# 06_B_RLight.net
KiCad netlist of a schematic drawn in EasyEDA Pro
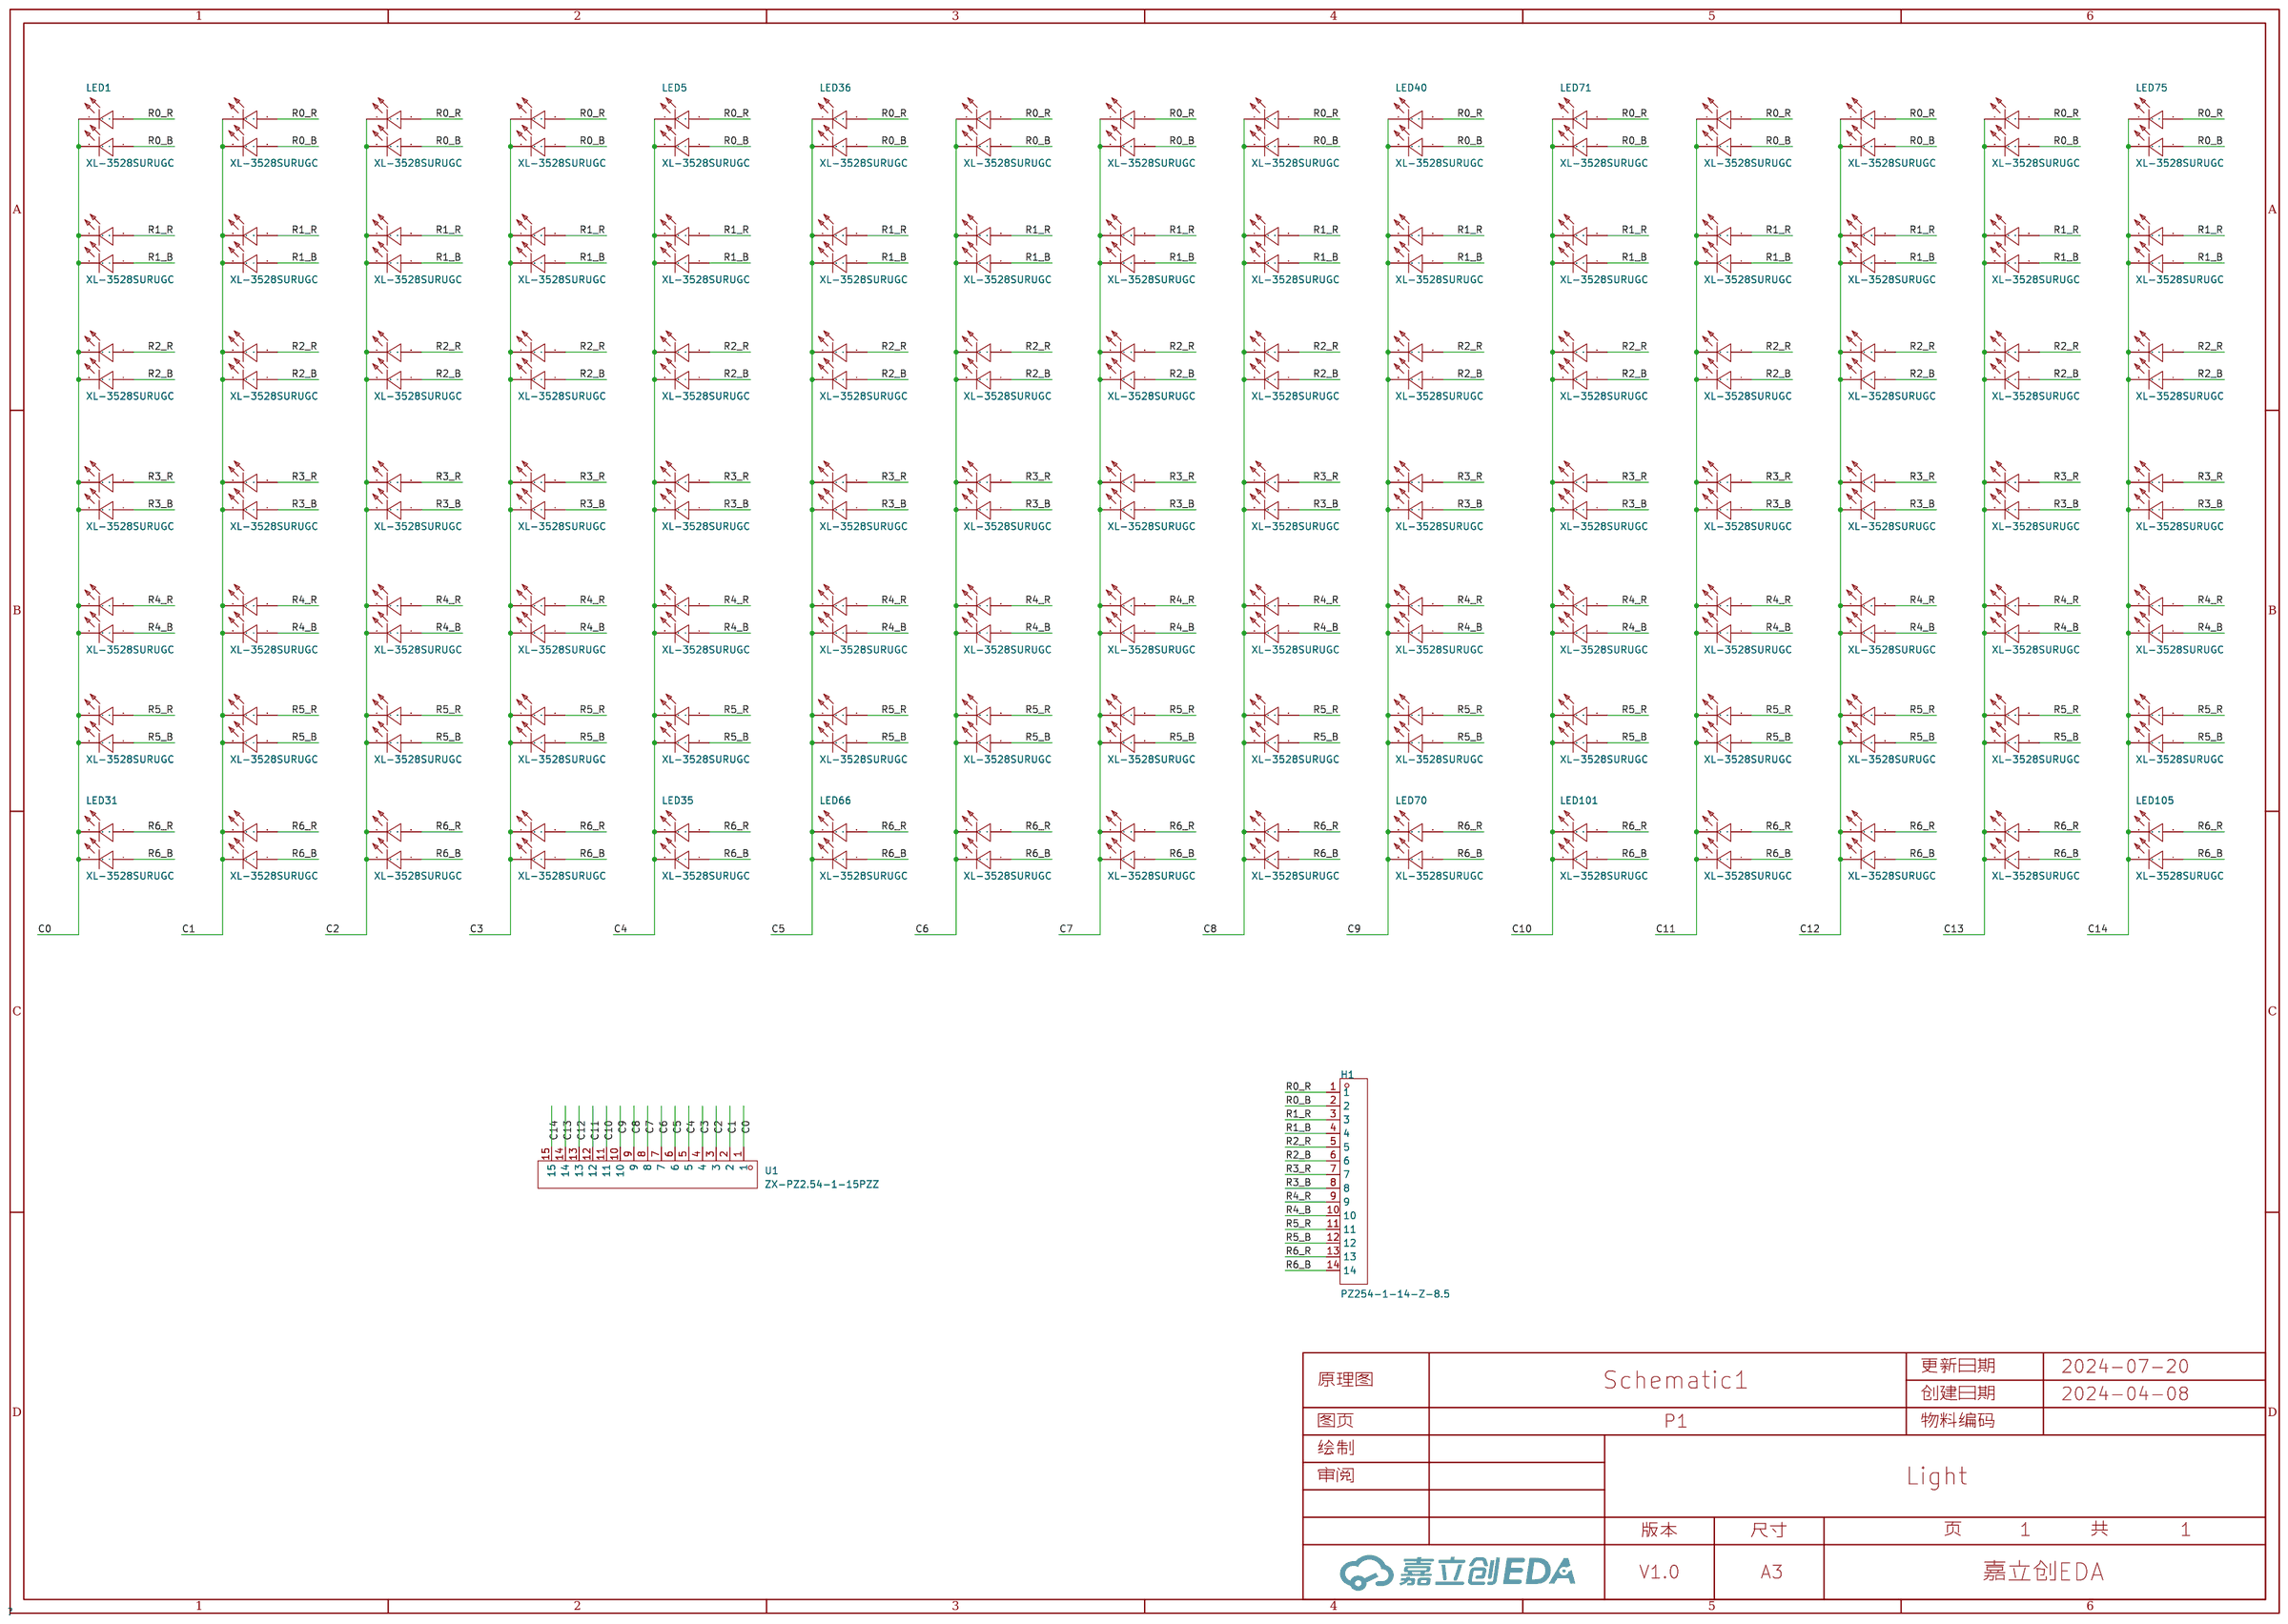
[diagram p0: schematic sheet]

(export (version "E")
  (design (tool "Eeschema 10.0.6"))
  (components
    (comp (ref "H1")
      (value "PZ254-1-14-Z-8.5")
      (footprint "easyedapro:HDR-TH_14P-P2.54-V-M")
      (fields (field (name "Manufacturer") "HCTL(华灿天禄)"))
      (libsource (lib "easyedapro") (part "PZ254-1-14-Z-8.5"))
    )
    (comp (ref "LED1")
      (value "XL-3528SURUGC")
      (footprint "easyedapro:LED-SMD_4P-L3.2-W2.8-LS3.5-TL")
      (fields (field (name "Manufacturer") "XINGLIGHT(成兴光)"))
      (libsource (lib "easyedapro") (part "XL-3528SURUGC"))
    )
    (comp (ref "LED2")
      (value "XL-3528SURUGC")
      (footprint "easyedapro:LED-SMD_4P-L3.2-W2.8-LS3.5-TL")
      (fields (field (name "Manufacturer") "XINGLIGHT(成兴光)"))
      (libsource (lib "easyedapro") (part "XL-3528SURUGC"))
    )
    (comp (ref "LED3")
      (value "XL-3528SURUGC")
      (footprint "easyedapro:LED-SMD_4P-L3.2-W2.8-LS3.5-TL")
      (fields (field (name "Manufacturer") "XINGLIGHT(成兴光)"))
      (libsource (lib "easyedapro") (part "XL-3528SURUGC"))
    )
    (comp (ref "LED4")
      (value "XL-3528SURUGC")
      (footprint "easyedapro:LED-SMD_4P-L3.2-W2.8-LS3.5-TL")
      (fields (field (name "Manufacturer") "XINGLIGHT(成兴光)"))
      (libsource (lib "easyedapro") (part "XL-3528SURUGC"))
    )
    (comp (ref "LED5")
      (value "XL-3528SURUGC")
      (footprint "easyedapro:LED-SMD_4P-L3.2-W2.8-LS3.5-TL")
      (fields (field (name "Manufacturer") "XINGLIGHT(成兴光)"))
      (libsource (lib "easyedapro") (part "XL-3528SURUGC"))
    )
    (comp (ref "LED6")
      (value "XL-3528SURUGC")
      (footprint "easyedapro:LED-SMD_4P-L3.2-W2.8-LS3.5-TL")
      (fields (field (name "Manufacturer") "XINGLIGHT(成兴光)"))
      (libsource (lib "easyedapro") (part "XL-3528SURUGC"))
    )
    (comp (ref "LED7")
      (value "XL-3528SURUGC")
      (footprint "easyedapro:LED-SMD_4P-L3.2-W2.8-LS3.5-TL")
      (fields (field (name "Manufacturer") "XINGLIGHT(成兴光)"))
      (libsource (lib "easyedapro") (part "XL-3528SURUGC"))
    )
    (comp (ref "LED8")
      (value "XL-3528SURUGC")
      (footprint "easyedapro:LED-SMD_4P-L3.2-W2.8-LS3.5-TL")
      (fields (field (name "Manufacturer") "XINGLIGHT(成兴光)"))
      (libsource (lib "easyedapro") (part "XL-3528SURUGC"))
    )
    (comp (ref "LED9")
      (value "XL-3528SURUGC")
      (footprint "easyedapro:LED-SMD_4P-L3.2-W2.8-LS3.5-TL")
      (fields (field (name "Manufacturer") "XINGLIGHT(成兴光)"))
      (libsource (lib "easyedapro") (part "XL-3528SURUGC"))
    )
    (comp (ref "LED10")
      (value "XL-3528SURUGC")
      (footprint "easyedapro:LED-SMD_4P-L3.2-W2.8-LS3.5-TL")
      (fields (field (name "Manufacturer") "XINGLIGHT(成兴光)"))
      (libsource (lib "easyedapro") (part "XL-3528SURUGC"))
    )
    (comp (ref "LED11")
      (value "XL-3528SURUGC")
      (footprint "easyedapro:LED-SMD_4P-L3.2-W2.8-LS3.5-TL")
      (fields (field (name "Manufacturer") "XINGLIGHT(成兴光)"))
      (libsource (lib "easyedapro") (part "XL-3528SURUGC"))
    )
    (comp (ref "LED12")
      (value "XL-3528SURUGC")
      (footprint "easyedapro:LED-SMD_4P-L3.2-W2.8-LS3.5-TL")
      (fields (field (name "Manufacturer") "XINGLIGHT(成兴光)"))
      (libsource (lib "easyedapro") (part "XL-3528SURUGC"))
    )
    (comp (ref "LED13")
      (value "XL-3528SURUGC")
      (footprint "easyedapro:LED-SMD_4P-L3.2-W2.8-LS3.5-TL")
      (fields (field (name "Manufacturer") "XINGLIGHT(成兴光)"))
      (libsource (lib "easyedapro") (part "XL-3528SURUGC"))
    )
    (comp (ref "LED14")
      (value "XL-3528SURUGC")
      (footprint "easyedapro:LED-SMD_4P-L3.2-W2.8-LS3.5-TL")
      (fields (field (name "Manufacturer") "XINGLIGHT(成兴光)"))
      (libsource (lib "easyedapro") (part "XL-3528SURUGC"))
    )
    (comp (ref "LED15")
      (value "XL-3528SURUGC")
      (footprint "easyedapro:LED-SMD_4P-L3.2-W2.8-LS3.5-TL")
      (fields (field (name "Manufacturer") "XINGLIGHT(成兴光)"))
      (libsource (lib "easyedapro") (part "XL-3528SURUGC"))
    )
    (comp (ref "LED16")
      (value "XL-3528SURUGC")
      (footprint "easyedapro:LED-SMD_4P-L3.2-W2.8-LS3.5-TL")
      (fields (field (name "Manufacturer") "XINGLIGHT(成兴光)"))
      (libsource (lib "easyedapro") (part "XL-3528SURUGC"))
    )
    (comp (ref "LED17")
      (value "XL-3528SURUGC")
      (footprint "easyedapro:LED-SMD_4P-L3.2-W2.8-LS3.5-TL")
      (fields (field (name "Manufacturer") "XINGLIGHT(成兴光)"))
      (libsource (lib "easyedapro") (part "XL-3528SURUGC"))
    )
    (comp (ref "LED18")
      (value "XL-3528SURUGC")
      (footprint "easyedapro:LED-SMD_4P-L3.2-W2.8-LS3.5-TL")
      (fields (field (name "Manufacturer") "XINGLIGHT(成兴光)"))
      (libsource (lib "easyedapro") (part "XL-3528SURUGC"))
    )
    (comp (ref "LED19")
      (value "XL-3528SURUGC")
      (footprint "easyedapro:LED-SMD_4P-L3.2-W2.8-LS3.5-TL")
      (fields (field (name "Manufacturer") "XINGLIGHT(成兴光)"))
      (libsource (lib "easyedapro") (part "XL-3528SURUGC"))
    )
    (comp (ref "LED20")
      (value "XL-3528SURUGC")
      (footprint "easyedapro:LED-SMD_4P-L3.2-W2.8-LS3.5-TL")
      (fields (field (name "Manufacturer") "XINGLIGHT(成兴光)"))
      (libsource (lib "easyedapro") (part "XL-3528SURUGC"))
    )
    (comp (ref "LED21")
      (value "XL-3528SURUGC")
      (footprint "easyedapro:LED-SMD_4P-L3.2-W2.8-LS3.5-TL")
      (fields (field (name "Manufacturer") "XINGLIGHT(成兴光)"))
      (libsource (lib "easyedapro") (part "XL-3528SURUGC"))
    )
    (comp (ref "LED22")
      (value "XL-3528SURUGC")
      (footprint "easyedapro:LED-SMD_4P-L3.2-W2.8-LS3.5-TL")
      (fields (field (name "Manufacturer") "XINGLIGHT(成兴光)"))
      (libsource (lib "easyedapro") (part "XL-3528SURUGC"))
    )
    (comp (ref "LED23")
      (value "XL-3528SURUGC")
      (footprint "easyedapro:LED-SMD_4P-L3.2-W2.8-LS3.5-TL")
      (fields (field (name "Manufacturer") "XINGLIGHT(成兴光)"))
      (libsource (lib "easyedapro") (part "XL-3528SURUGC"))
    )
    (comp (ref "LED24")
      (value "XL-3528SURUGC")
      (footprint "easyedapro:LED-SMD_4P-L3.2-W2.8-LS3.5-TL")
      (fields (field (name "Manufacturer") "XINGLIGHT(成兴光)"))
      (libsource (lib "easyedapro") (part "XL-3528SURUGC"))
    )
    (comp (ref "LED25")
      (value "XL-3528SURUGC")
      (footprint "easyedapro:LED-SMD_4P-L3.2-W2.8-LS3.5-TL")
      (fields (field (name "Manufacturer") "XINGLIGHT(成兴光)"))
      (libsource (lib "easyedapro") (part "XL-3528SURUGC"))
    )
    (comp (ref "LED26")
      (value "XL-3528SURUGC")
      (footprint "easyedapro:LED-SMD_4P-L3.2-W2.8-LS3.5-TL")
      (fields (field (name "Manufacturer") "XINGLIGHT(成兴光)"))
      (libsource (lib "easyedapro") (part "XL-3528SURUGC"))
    )
    (comp (ref "LED27")
      (value "XL-3528SURUGC")
      (footprint "easyedapro:LED-SMD_4P-L3.2-W2.8-LS3.5-TL")
      (fields (field (name "Manufacturer") "XINGLIGHT(成兴光)"))
      (libsource (lib "easyedapro") (part "XL-3528SURUGC"))
    )
    (comp (ref "LED28")
      (value "XL-3528SURUGC")
      (footprint "easyedapro:LED-SMD_4P-L3.2-W2.8-LS3.5-TL")
      (fields (field (name "Manufacturer") "XINGLIGHT(成兴光)"))
      (libsource (lib "easyedapro") (part "XL-3528SURUGC"))
    )
    (comp (ref "LED29")
      (value "XL-3528SURUGC")
      (footprint "easyedapro:LED-SMD_4P-L3.2-W2.8-LS3.5-TL")
      (fields (field (name "Manufacturer") "XINGLIGHT(成兴光)"))
      (libsource (lib "easyedapro") (part "XL-3528SURUGC"))
    )
    (comp (ref "LED30")
      (value "XL-3528SURUGC")
      (footprint "easyedapro:LED-SMD_4P-L3.2-W2.8-LS3.5-TL")
      (fields (field (name "Manufacturer") "XINGLIGHT(成兴光)"))
      (libsource (lib "easyedapro") (part "XL-3528SURUGC"))
    )
    (comp (ref "LED31")
      (value "XL-3528SURUGC")
      (footprint "easyedapro:LED-SMD_4P-L3.2-W2.8-LS3.5-TL")
      (fields (field (name "Manufacturer") "XINGLIGHT(成兴光)"))
      (libsource (lib "easyedapro") (part "XL-3528SURUGC"))
    )
    (comp (ref "LED32")
      (value "XL-3528SURUGC")
      (footprint "easyedapro:LED-SMD_4P-L3.2-W2.8-LS3.5-TL")
      (fields (field (name "Manufacturer") "XINGLIGHT(成兴光)"))
      (libsource (lib "easyedapro") (part "XL-3528SURUGC"))
    )
    (comp (ref "LED33")
      (value "XL-3528SURUGC")
      (footprint "easyedapro:LED-SMD_4P-L3.2-W2.8-LS3.5-TL")
      (fields (field (name "Manufacturer") "XINGLIGHT(成兴光)"))
      (libsource (lib "easyedapro") (part "XL-3528SURUGC"))
    )
    (comp (ref "LED34")
      (value "XL-3528SURUGC")
      (footprint "easyedapro:LED-SMD_4P-L3.2-W2.8-LS3.5-TL")
      (fields (field (name "Manufacturer") "XINGLIGHT(成兴光)"))
      (libsource (lib "easyedapro") (part "XL-3528SURUGC"))
    )
    (comp (ref "LED35")
      (value "XL-3528SURUGC")
      (footprint "easyedapro:LED-SMD_4P-L3.2-W2.8-LS3.5-TL")
      (fields (field (name "Manufacturer") "XINGLIGHT(成兴光)"))
      (libsource (lib "easyedapro") (part "XL-3528SURUGC"))
    )
    (comp (ref "LED36")
      (value "XL-3528SURUGC")
      (footprint "easyedapro:LED-SMD_4P-L3.2-W2.8-LS3.5-TL")
      (fields (field (name "Manufacturer") "XINGLIGHT(成兴光)"))
      (libsource (lib "easyedapro") (part "XL-3528SURUGC"))
    )
    (comp (ref "LED37")
      (value "XL-3528SURUGC")
      (footprint "easyedapro:LED-SMD_4P-L3.2-W2.8-LS3.5-TL")
      (fields (field (name "Manufacturer") "XINGLIGHT(成兴光)"))
      (libsource (lib "easyedapro") (part "XL-3528SURUGC"))
    )
    (comp (ref "LED38")
      (value "XL-3528SURUGC")
      (footprint "easyedapro:LED-SMD_4P-L3.2-W2.8-LS3.5-TL")
      (fields (field (name "Manufacturer") "XINGLIGHT(成兴光)"))
      (libsource (lib "easyedapro") (part "XL-3528SURUGC"))
    )
    (comp (ref "LED39")
      (value "XL-3528SURUGC")
      (footprint "easyedapro:LED-SMD_4P-L3.2-W2.8-LS3.5-TL")
      (fields (field (name "Manufacturer") "XINGLIGHT(成兴光)"))
      (libsource (lib "easyedapro") (part "XL-3528SURUGC"))
    )
    (comp (ref "LED40")
      (value "XL-3528SURUGC")
      (footprint "easyedapro:LED-SMD_4P-L3.2-W2.8-LS3.5-TL")
      (fields (field (name "Manufacturer") "XINGLIGHT(成兴光)"))
      (libsource (lib "easyedapro") (part "XL-3528SURUGC"))
    )
    (comp (ref "LED41")
      (value "XL-3528SURUGC")
      (footprint "easyedapro:LED-SMD_4P-L3.2-W2.8-LS3.5-TL")
      (fields (field (name "Manufacturer") "XINGLIGHT(成兴光)"))
      (libsource (lib "easyedapro") (part "XL-3528SURUGC"))
    )
    (comp (ref "LED42")
      (value "XL-3528SURUGC")
      (footprint "easyedapro:LED-SMD_4P-L3.2-W2.8-LS3.5-TL")
      (fields (field (name "Manufacturer") "XINGLIGHT(成兴光)"))
      (libsource (lib "easyedapro") (part "XL-3528SURUGC"))
    )
    (comp (ref "LED43")
      (value "XL-3528SURUGC")
      (footprint "easyedapro:LED-SMD_4P-L3.2-W2.8-LS3.5-TL")
      (fields (field (name "Manufacturer") "XINGLIGHT(成兴光)"))
      (libsource (lib "easyedapro") (part "XL-3528SURUGC"))
    )
    (comp (ref "LED44")
      (value "XL-3528SURUGC")
      (footprint "easyedapro:LED-SMD_4P-L3.2-W2.8-LS3.5-TL")
      (fields (field (name "Manufacturer") "XINGLIGHT(成兴光)"))
      (libsource (lib "easyedapro") (part "XL-3528SURUGC"))
    )
    (comp (ref "LED45")
      (value "XL-3528SURUGC")
      (footprint "easyedapro:LED-SMD_4P-L3.2-W2.8-LS3.5-TL")
      (fields (field (name "Manufacturer") "XINGLIGHT(成兴光)"))
      (libsource (lib "easyedapro") (part "XL-3528SURUGC"))
    )
    (comp (ref "LED46")
      (value "XL-3528SURUGC")
      (footprint "easyedapro:LED-SMD_4P-L3.2-W2.8-LS3.5-TL")
      (fields (field (name "Manufacturer") "XINGLIGHT(成兴光)"))
      (libsource (lib "easyedapro") (part "XL-3528SURUGC"))
    )
    (comp (ref "LED47")
      (value "XL-3528SURUGC")
      (footprint "easyedapro:LED-SMD_4P-L3.2-W2.8-LS3.5-TL")
      (fields (field (name "Manufacturer") "XINGLIGHT(成兴光)"))
      (libsource (lib "easyedapro") (part "XL-3528SURUGC"))
    )
    (comp (ref "LED48")
      (value "XL-3528SURUGC")
      (footprint "easyedapro:LED-SMD_4P-L3.2-W2.8-LS3.5-TL")
      (fields (field (name "Manufacturer") "XINGLIGHT(成兴光)"))
      (libsource (lib "easyedapro") (part "XL-3528SURUGC"))
    )
    (comp (ref "LED49")
      (value "XL-3528SURUGC")
      (footprint "easyedapro:LED-SMD_4P-L3.2-W2.8-LS3.5-TL")
      (fields (field (name "Manufacturer") "XINGLIGHT(成兴光)"))
      (libsource (lib "easyedapro") (part "XL-3528SURUGC"))
    )
    (comp (ref "LED50")
      (value "XL-3528SURUGC")
      (footprint "easyedapro:LED-SMD_4P-L3.2-W2.8-LS3.5-TL")
      (fields (field (name "Manufacturer") "XINGLIGHT(成兴光)"))
      (libsource (lib "easyedapro") (part "XL-3528SURUGC"))
    )
    (comp (ref "LED51")
      (value "XL-3528SURUGC")
      (footprint "easyedapro:LED-SMD_4P-L3.2-W2.8-LS3.5-TL")
      (fields (field (name "Manufacturer") "XINGLIGHT(成兴光)"))
      (libsource (lib "easyedapro") (part "XL-3528SURUGC"))
    )
    (comp (ref "LED52")
      (value "XL-3528SURUGC")
      (footprint "easyedapro:LED-SMD_4P-L3.2-W2.8-LS3.5-TL")
      (fields (field (name "Manufacturer") "XINGLIGHT(成兴光)"))
      (libsource (lib "easyedapro") (part "XL-3528SURUGC"))
    )
    (comp (ref "LED53")
      (value "XL-3528SURUGC")
      (footprint "easyedapro:LED-SMD_4P-L3.2-W2.8-LS3.5-TL")
      (fields (field (name "Manufacturer") "XINGLIGHT(成兴光)"))
      (libsource (lib "easyedapro") (part "XL-3528SURUGC"))
    )
    (comp (ref "LED54")
      (value "XL-3528SURUGC")
      (footprint "easyedapro:LED-SMD_4P-L3.2-W2.8-LS3.5-TL")
      (fields (field (name "Manufacturer") "XINGLIGHT(成兴光)"))
      (libsource (lib "easyedapro") (part "XL-3528SURUGC"))
    )
    (comp (ref "LED55")
      (value "XL-3528SURUGC")
      (footprint "easyedapro:LED-SMD_4P-L3.2-W2.8-LS3.5-TL")
      (fields (field (name "Manufacturer") "XINGLIGHT(成兴光)"))
      (libsource (lib "easyedapro") (part "XL-3528SURUGC"))
    )
    (comp (ref "LED56")
      (value "XL-3528SURUGC")
      (footprint "easyedapro:LED-SMD_4P-L3.2-W2.8-LS3.5-TL")
      (fields (field (name "Manufacturer") "XINGLIGHT(成兴光)"))
      (libsource (lib "easyedapro") (part "XL-3528SURUGC"))
    )
    (comp (ref "LED57")
      (value "XL-3528SURUGC")
      (footprint "easyedapro:LED-SMD_4P-L3.2-W2.8-LS3.5-TL")
      (fields (field (name "Manufacturer") "XINGLIGHT(成兴光)"))
      (libsource (lib "easyedapro") (part "XL-3528SURUGC"))
    )
    (comp (ref "LED58")
      (value "XL-3528SURUGC")
      (footprint "easyedapro:LED-SMD_4P-L3.2-W2.8-LS3.5-TL")
      (fields (field (name "Manufacturer") "XINGLIGHT(成兴光)"))
      (libsource (lib "easyedapro") (part "XL-3528SURUGC"))
    )
    (comp (ref "LED59")
      (value "XL-3528SURUGC")
      (footprint "easyedapro:LED-SMD_4P-L3.2-W2.8-LS3.5-TL")
      (fields (field (name "Manufacturer") "XINGLIGHT(成兴光)"))
      (libsource (lib "easyedapro") (part "XL-3528SURUGC"))
    )
    (comp (ref "LED60")
      (value "XL-3528SURUGC")
      (footprint "easyedapro:LED-SMD_4P-L3.2-W2.8-LS3.5-TL")
      (fields (field (name "Manufacturer") "XINGLIGHT(成兴光)"))
      (libsource (lib "easyedapro") (part "XL-3528SURUGC"))
    )
    (comp (ref "LED61")
      (value "XL-3528SURUGC")
      (footprint "easyedapro:LED-SMD_4P-L3.2-W2.8-LS3.5-TL")
      (fields (field (name "Manufacturer") "XINGLIGHT(成兴光)"))
      (libsource (lib "easyedapro") (part "XL-3528SURUGC"))
    )
    (comp (ref "LED62")
      (value "XL-3528SURUGC")
      (footprint "easyedapro:LED-SMD_4P-L3.2-W2.8-LS3.5-TL")
      (fields (field (name "Manufacturer") "XINGLIGHT(成兴光)"))
      (libsource (lib "easyedapro") (part "XL-3528SURUGC"))
    )
    (comp (ref "LED63")
      (value "XL-3528SURUGC")
      (footprint "easyedapro:LED-SMD_4P-L3.2-W2.8-LS3.5-TL")
      (fields (field (name "Manufacturer") "XINGLIGHT(成兴光)"))
      (libsource (lib "easyedapro") (part "XL-3528SURUGC"))
    )
    (comp (ref "LED64")
      (value "XL-3528SURUGC")
      (footprint "easyedapro:LED-SMD_4P-L3.2-W2.8-LS3.5-TL")
      (fields (field (name "Manufacturer") "XINGLIGHT(成兴光)"))
      (libsource (lib "easyedapro") (part "XL-3528SURUGC"))
    )
    (comp (ref "LED65")
      (value "XL-3528SURUGC")
      (footprint "easyedapro:LED-SMD_4P-L3.2-W2.8-LS3.5-TL")
      (fields (field (name "Manufacturer") "XINGLIGHT(成兴光)"))
      (libsource (lib "easyedapro") (part "XL-3528SURUGC"))
    )
    (comp (ref "LED66")
      (value "XL-3528SURUGC")
      (footprint "easyedapro:LED-SMD_4P-L3.2-W2.8-LS3.5-TL")
      (fields (field (name "Manufacturer") "XINGLIGHT(成兴光)"))
      (libsource (lib "easyedapro") (part "XL-3528SURUGC"))
    )
    (comp (ref "LED67")
      (value "XL-3528SURUGC")
      (footprint "easyedapro:LED-SMD_4P-L3.2-W2.8-LS3.5-TL")
      (fields (field (name "Manufacturer") "XINGLIGHT(成兴光)"))
      (libsource (lib "easyedapro") (part "XL-3528SURUGC"))
    )
    (comp (ref "LED68")
      (value "XL-3528SURUGC")
      (footprint "easyedapro:LED-SMD_4P-L3.2-W2.8-LS3.5-TL")
      (fields (field (name "Manufacturer") "XINGLIGHT(成兴光)"))
      (libsource (lib "easyedapro") (part "XL-3528SURUGC"))
    )
    (comp (ref "LED69")
      (value "XL-3528SURUGC")
      (footprint "easyedapro:LED-SMD_4P-L3.2-W2.8-LS3.5-TL")
      (fields (field (name "Manufacturer") "XINGLIGHT(成兴光)"))
      (libsource (lib "easyedapro") (part "XL-3528SURUGC"))
    )
    (comp (ref "LED70")
      (value "XL-3528SURUGC")
      (footprint "easyedapro:LED-SMD_4P-L3.2-W2.8-LS3.5-TL")
      (fields (field (name "Manufacturer") "XINGLIGHT(成兴光)"))
      (libsource (lib "easyedapro") (part "XL-3528SURUGC"))
    )
    (comp (ref "LED71")
      (value "XL-3528SURUGC")
      (footprint "easyedapro:LED-SMD_4P-L3.2-W2.8-LS3.5-TL")
      (fields (field (name "Manufacturer") "XINGLIGHT(成兴光)"))
      (libsource (lib "easyedapro") (part "XL-3528SURUGC"))
    )
    (comp (ref "LED72")
      (value "XL-3528SURUGC")
      (footprint "easyedapro:LED-SMD_4P-L3.2-W2.8-LS3.5-TL")
      (fields (field (name "Manufacturer") "XINGLIGHT(成兴光)"))
      (libsource (lib "easyedapro") (part "XL-3528SURUGC"))
    )
    (comp (ref "LED73")
      (value "XL-3528SURUGC")
      (footprint "easyedapro:LED-SMD_4P-L3.2-W2.8-LS3.5-TL")
      (fields (field (name "Manufacturer") "XINGLIGHT(成兴光)"))
      (libsource (lib "easyedapro") (part "XL-3528SURUGC"))
    )
    (comp (ref "LED74")
      (value "XL-3528SURUGC")
      (footprint "easyedapro:LED-SMD_4P-L3.2-W2.8-LS3.5-TL")
      (fields (field (name "Manufacturer") "XINGLIGHT(成兴光)"))
      (libsource (lib "easyedapro") (part "XL-3528SURUGC"))
    )
    (comp (ref "LED75")
      (value "XL-3528SURUGC")
      (footprint "easyedapro:LED-SMD_4P-L3.2-W2.8-LS3.5-TL")
      (fields (field (name "Manufacturer") "XINGLIGHT(成兴光)"))
      (libsource (lib "easyedapro") (part "XL-3528SURUGC"))
    )
    (comp (ref "LED76")
      (value "XL-3528SURUGC")
      (footprint "easyedapro:LED-SMD_4P-L3.2-W2.8-LS3.5-TL")
      (fields (field (name "Manufacturer") "XINGLIGHT(成兴光)"))
      (libsource (lib "easyedapro") (part "XL-3528SURUGC"))
    )
    (comp (ref "LED77")
      (value "XL-3528SURUGC")
      (footprint "easyedapro:LED-SMD_4P-L3.2-W2.8-LS3.5-TL")
      (fields (field (name "Manufacturer") "XINGLIGHT(成兴光)"))
      (libsource (lib "easyedapro") (part "XL-3528SURUGC"))
    )
    (comp (ref "LED78")
      (value "XL-3528SURUGC")
      (footprint "easyedapro:LED-SMD_4P-L3.2-W2.8-LS3.5-TL")
      (fields (field (name "Manufacturer") "XINGLIGHT(成兴光)"))
      (libsource (lib "easyedapro") (part "XL-3528SURUGC"))
    )
    (comp (ref "LED79")
      (value "XL-3528SURUGC")
      (footprint "easyedapro:LED-SMD_4P-L3.2-W2.8-LS3.5-TL")
      (fields (field (name "Manufacturer") "XINGLIGHT(成兴光)"))
      (libsource (lib "easyedapro") (part "XL-3528SURUGC"))
    )
    (comp (ref "LED80")
      (value "XL-3528SURUGC")
      (footprint "easyedapro:LED-SMD_4P-L3.2-W2.8-LS3.5-TL")
      (fields (field (name "Manufacturer") "XINGLIGHT(成兴光)"))
      (libsource (lib "easyedapro") (part "XL-3528SURUGC"))
    )
    (comp (ref "LED81")
      (value "XL-3528SURUGC")
      (footprint "easyedapro:LED-SMD_4P-L3.2-W2.8-LS3.5-TL")
      (fields (field (name "Manufacturer") "XINGLIGHT(成兴光)"))
      (libsource (lib "easyedapro") (part "XL-3528SURUGC"))
    )
    (comp (ref "LED82")
      (value "XL-3528SURUGC")
      (footprint "easyedapro:LED-SMD_4P-L3.2-W2.8-LS3.5-TL")
      (fields (field (name "Manufacturer") "XINGLIGHT(成兴光)"))
      (libsource (lib "easyedapro") (part "XL-3528SURUGC"))
    )
    (comp (ref "LED83")
      (value "XL-3528SURUGC")
      (footprint "easyedapro:LED-SMD_4P-L3.2-W2.8-LS3.5-TL")
      (fields (field (name "Manufacturer") "XINGLIGHT(成兴光)"))
      (libsource (lib "easyedapro") (part "XL-3528SURUGC"))
    )
    (comp (ref "LED84")
      (value "XL-3528SURUGC")
      (footprint "easyedapro:LED-SMD_4P-L3.2-W2.8-LS3.5-TL")
      (fields (field (name "Manufacturer") "XINGLIGHT(成兴光)"))
      (libsource (lib "easyedapro") (part "XL-3528SURUGC"))
    )
    (comp (ref "LED85")
      (value "XL-3528SURUGC")
      (footprint "easyedapro:LED-SMD_4P-L3.2-W2.8-LS3.5-TL")
      (fields (field (name "Manufacturer") "XINGLIGHT(成兴光)"))
      (libsource (lib "easyedapro") (part "XL-3528SURUGC"))
    )
    (comp (ref "LED86")
      (value "XL-3528SURUGC")
      (footprint "easyedapro:LED-SMD_4P-L3.2-W2.8-LS3.5-TL")
      (fields (field (name "Manufacturer") "XINGLIGHT(成兴光)"))
      (libsource (lib "easyedapro") (part "XL-3528SURUGC"))
    )
    (comp (ref "LED87")
      (value "XL-3528SURUGC")
      (footprint "easyedapro:LED-SMD_4P-L3.2-W2.8-LS3.5-TL")
      (fields (field (name "Manufacturer") "XINGLIGHT(成兴光)"))
      (libsource (lib "easyedapro") (part "XL-3528SURUGC"))
    )
    (comp (ref "LED88")
      (value "XL-3528SURUGC")
      (footprint "easyedapro:LED-SMD_4P-L3.2-W2.8-LS3.5-TL")
      (fields (field (name "Manufacturer") "XINGLIGHT(成兴光)"))
      (libsource (lib "easyedapro") (part "XL-3528SURUGC"))
    )
    (comp (ref "LED89")
      (value "XL-3528SURUGC")
      (footprint "easyedapro:LED-SMD_4P-L3.2-W2.8-LS3.5-TL")
      (fields (field (name "Manufacturer") "XINGLIGHT(成兴光)"))
      (libsource (lib "easyedapro") (part "XL-3528SURUGC"))
    )
    (comp (ref "LED90")
      (value "XL-3528SURUGC")
      (footprint "easyedapro:LED-SMD_4P-L3.2-W2.8-LS3.5-TL")
      (fields (field (name "Manufacturer") "XINGLIGHT(成兴光)"))
      (libsource (lib "easyedapro") (part "XL-3528SURUGC"))
    )
    (comp (ref "LED91")
      (value "XL-3528SURUGC")
      (footprint "easyedapro:LED-SMD_4P-L3.2-W2.8-LS3.5-TL")
      (fields (field (name "Manufacturer") "XINGLIGHT(成兴光)"))
      (libsource (lib "easyedapro") (part "XL-3528SURUGC"))
    )
    (comp (ref "LED92")
      (value "XL-3528SURUGC")
      (footprint "easyedapro:LED-SMD_4P-L3.2-W2.8-LS3.5-TL")
      (fields (field (name "Manufacturer") "XINGLIGHT(成兴光)"))
      (libsource (lib "easyedapro") (part "XL-3528SURUGC"))
    )
    (comp (ref "LED93")
      (value "XL-3528SURUGC")
      (footprint "easyedapro:LED-SMD_4P-L3.2-W2.8-LS3.5-TL")
      (fields (field (name "Manufacturer") "XINGLIGHT(成兴光)"))
      (libsource (lib "easyedapro") (part "XL-3528SURUGC"))
    )
    (comp (ref "LED94")
      (value "XL-3528SURUGC")
      (footprint "easyedapro:LED-SMD_4P-L3.2-W2.8-LS3.5-TL")
      (fields (field (name "Manufacturer") "XINGLIGHT(成兴光)"))
      (libsource (lib "easyedapro") (part "XL-3528SURUGC"))
    )
    (comp (ref "LED95")
      (value "XL-3528SURUGC")
      (footprint "easyedapro:LED-SMD_4P-L3.2-W2.8-LS3.5-TL")
      (fields (field (name "Manufacturer") "XINGLIGHT(成兴光)"))
      (libsource (lib "easyedapro") (part "XL-3528SURUGC"))
    )
    (comp (ref "LED96")
      (value "XL-3528SURUGC")
      (footprint "easyedapro:LED-SMD_4P-L3.2-W2.8-LS3.5-TL")
      (fields (field (name "Manufacturer") "XINGLIGHT(成兴光)"))
      (libsource (lib "easyedapro") (part "XL-3528SURUGC"))
    )
    (comp (ref "LED97")
      (value "XL-3528SURUGC")
      (footprint "easyedapro:LED-SMD_4P-L3.2-W2.8-LS3.5-TL")
      (fields (field (name "Manufacturer") "XINGLIGHT(成兴光)"))
      (libsource (lib "easyedapro") (part "XL-3528SURUGC"))
    )
    (comp (ref "LED98")
      (value "XL-3528SURUGC")
      (footprint "easyedapro:LED-SMD_4P-L3.2-W2.8-LS3.5-TL")
      (fields (field (name "Manufacturer") "XINGLIGHT(成兴光)"))
      (libsource (lib "easyedapro") (part "XL-3528SURUGC"))
    )
    (comp (ref "LED99")
      (value "XL-3528SURUGC")
      (footprint "easyedapro:LED-SMD_4P-L3.2-W2.8-LS3.5-TL")
      (fields (field (name "Manufacturer") "XINGLIGHT(成兴光)"))
      (libsource (lib "easyedapro") (part "XL-3528SURUGC"))
    )
    (comp (ref "LED100")
      (value "XL-3528SURUGC")
      (footprint "easyedapro:LED-SMD_4P-L3.2-W2.8-LS3.5-TL")
      (fields (field (name "Manufacturer") "XINGLIGHT(成兴光)"))
      (libsource (lib "easyedapro") (part "XL-3528SURUGC"))
    )
    (comp (ref "LED101")
      (value "XL-3528SURUGC")
      (footprint "easyedapro:LED-SMD_4P-L3.2-W2.8-LS3.5-TL")
      (fields (field (name "Manufacturer") "XINGLIGHT(成兴光)"))
      (libsource (lib "easyedapro") (part "XL-3528SURUGC"))
    )
    (comp (ref "LED102")
      (value "XL-3528SURUGC")
      (footprint "easyedapro:LED-SMD_4P-L3.2-W2.8-LS3.5-TL")
      (fields (field (name "Manufacturer") "XINGLIGHT(成兴光)"))
      (libsource (lib "easyedapro") (part "XL-3528SURUGC"))
    )
    (comp (ref "LED103")
      (value "XL-3528SURUGC")
      (footprint "easyedapro:LED-SMD_4P-L3.2-W2.8-LS3.5-TL")
      (fields (field (name "Manufacturer") "XINGLIGHT(成兴光)"))
      (libsource (lib "easyedapro") (part "XL-3528SURUGC"))
    )
    (comp (ref "LED104")
      (value "XL-3528SURUGC")
      (footprint "easyedapro:LED-SMD_4P-L3.2-W2.8-LS3.5-TL")
      (fields (field (name "Manufacturer") "XINGLIGHT(成兴光)"))
      (libsource (lib "easyedapro") (part "XL-3528SURUGC"))
    )
    (comp (ref "LED105")
      (value "XL-3528SURUGC")
      (footprint "easyedapro:LED-SMD_4P-L3.2-W2.8-LS3.5-TL")
      (fields (field (name "Manufacturer") "XINGLIGHT(成兴光)"))
      (libsource (lib "easyedapro") (part "XL-3528SURUGC"))
    )
    (comp (ref "U1")
      (value "ZX-PZ2.54-1-15PZZ")
      (footprint "easyedapro:HDR-TH_15P-P2.54-V-M")
      (fields (field (name "Manufacturer") "Megastar(兆星)"))
      (libsource (lib "easyedapro") (part "ZX-PZ2.54-1-15PZZ"))
    )
  )
  (nets
    (net (code "1") (name "/C0") (class "Default")
      (node (ref "LED1") (pin "1") (pinfunction "1_1") (pintype "unspecified"))
      (node (ref "LED1") (pin "3") (pinfunction "3_3") (pintype "unspecified"))
      (node (ref "LED11") (pin "1") (pinfunction "1_1") (pintype "unspecified"))
      (node (ref "LED11") (pin "3") (pinfunction "3_3") (pintype "unspecified"))
      (node (ref "LED16") (pin "1") (pinfunction "1_1") (pintype "unspecified"))
      (node (ref "LED16") (pin "3") (pinfunction "3_3") (pintype "unspecified"))
      (node (ref "LED21") (pin "1") (pinfunction "1_1") (pintype "unspecified"))
      (node (ref "LED21") (pin "3") (pinfunction "3_3") (pintype "unspecified"))
      (node (ref "LED26") (pin "1") (pinfunction "1_1") (pintype "unspecified"))
      (node (ref "LED26") (pin "3") (pinfunction "3_3") (pintype "unspecified"))
      (node (ref "LED31") (pin "1") (pinfunction "1_1") (pintype "unspecified"))
      (node (ref "LED31") (pin "3") (pinfunction "3_3") (pintype "unspecified"))
      (node (ref "LED6") (pin "1") (pinfunction "1_1") (pintype "unspecified"))
      (node (ref "LED6") (pin "3") (pinfunction "3_3") (pintype "unspecified"))
      (node (ref "U1") (pin "1") (pinfunction "1_1") (pintype "unspecified"))
    )
    (net (code "2") (name "/C1") (class "Default")
      (node (ref "LED12") (pin "1") (pinfunction "1_1") (pintype "unspecified"))
      (node (ref "LED12") (pin "3") (pinfunction "3_3") (pintype "unspecified"))
      (node (ref "LED17") (pin "1") (pinfunction "1_1") (pintype "unspecified"))
      (node (ref "LED17") (pin "3") (pinfunction "3_3") (pintype "unspecified"))
      (node (ref "LED2") (pin "1") (pinfunction "1_1") (pintype "unspecified"))
      (node (ref "LED2") (pin "3") (pinfunction "3_3") (pintype "unspecified"))
      (node (ref "LED22") (pin "1") (pinfunction "1_1") (pintype "unspecified"))
      (node (ref "LED22") (pin "3") (pinfunction "3_3") (pintype "unspecified"))
      (node (ref "LED27") (pin "1") (pinfunction "1_1") (pintype "unspecified"))
      (node (ref "LED27") (pin "3") (pinfunction "3_3") (pintype "unspecified"))
      (node (ref "LED32") (pin "1") (pinfunction "1_1") (pintype "unspecified"))
      (node (ref "LED32") (pin "3") (pinfunction "3_3") (pintype "unspecified"))
      (node (ref "LED7") (pin "1") (pinfunction "1_1") (pintype "unspecified"))
      (node (ref "LED7") (pin "3") (pinfunction "3_3") (pintype "unspecified"))
      (node (ref "U1") (pin "2") (pinfunction "2_2") (pintype "unspecified"))
    )
    (net (code "3") (name "/C2") (class "Default")
      (node (ref "LED13") (pin "1") (pinfunction "1_1") (pintype "unspecified"))
      (node (ref "LED13") (pin "3") (pinfunction "3_3") (pintype "unspecified"))
      (node (ref "LED18") (pin "1") (pinfunction "1_1") (pintype "unspecified"))
      (node (ref "LED18") (pin "3") (pinfunction "3_3") (pintype "unspecified"))
      (node (ref "LED23") (pin "1") (pinfunction "1_1") (pintype "unspecified"))
      (node (ref "LED23") (pin "3") (pinfunction "3_3") (pintype "unspecified"))
      (node (ref "LED28") (pin "1") (pinfunction "1_1") (pintype "unspecified"))
      (node (ref "LED28") (pin "3") (pinfunction "3_3") (pintype "unspecified"))
      (node (ref "LED3") (pin "1") (pinfunction "1_1") (pintype "unspecified"))
      (node (ref "LED3") (pin "3") (pinfunction "3_3") (pintype "unspecified"))
      (node (ref "LED33") (pin "1") (pinfunction "1_1") (pintype "unspecified"))
      (node (ref "LED33") (pin "3") (pinfunction "3_3") (pintype "unspecified"))
      (node (ref "LED8") (pin "1") (pinfunction "1_1") (pintype "unspecified"))
      (node (ref "LED8") (pin "3") (pinfunction "3_3") (pintype "unspecified"))
      (node (ref "U1") (pin "3") (pinfunction "3_3") (pintype "unspecified"))
    )
    (net (code "4") (name "/C3") (class "Default")
      (node (ref "LED14") (pin "1") (pinfunction "1_1") (pintype "unspecified"))
      (node (ref "LED14") (pin "3") (pinfunction "3_3") (pintype "unspecified"))
      (node (ref "LED19") (pin "1") (pinfunction "1_1") (pintype "unspecified"))
      (node (ref "LED19") (pin "3") (pinfunction "3_3") (pintype "unspecified"))
      (node (ref "LED24") (pin "1") (pinfunction "1_1") (pintype "unspecified"))
      (node (ref "LED24") (pin "3") (pinfunction "3_3") (pintype "unspecified"))
      (node (ref "LED29") (pin "1") (pinfunction "1_1") (pintype "unspecified"))
      (node (ref "LED29") (pin "3") (pinfunction "3_3") (pintype "unspecified"))
      (node (ref "LED34") (pin "1") (pinfunction "1_1") (pintype "unspecified"))
      (node (ref "LED34") (pin "3") (pinfunction "3_3") (pintype "unspecified"))
      (node (ref "LED4") (pin "1") (pinfunction "1_1") (pintype "unspecified"))
      (node (ref "LED4") (pin "3") (pinfunction "3_3") (pintype "unspecified"))
      (node (ref "LED9") (pin "1") (pinfunction "1_1") (pintype "unspecified"))
      (node (ref "LED9") (pin "3") (pinfunction "3_3") (pintype "unspecified"))
      (node (ref "U1") (pin "4") (pinfunction "4_4") (pintype "unspecified"))
    )
    (net (code "5") (name "/C4") (class "Default")
      (node (ref "LED10") (pin "1") (pinfunction "1_1") (pintype "unspecified"))
      (node (ref "LED10") (pin "3") (pinfunction "3_3") (pintype "unspecified"))
      (node (ref "LED15") (pin "1") (pinfunction "1_1") (pintype "unspecified"))
      (node (ref "LED15") (pin "3") (pinfunction "3_3") (pintype "unspecified"))
      (node (ref "LED20") (pin "1") (pinfunction "1_1") (pintype "unspecified"))
      (node (ref "LED20") (pin "3") (pinfunction "3_3") (pintype "unspecified"))
      (node (ref "LED25") (pin "1") (pinfunction "1_1") (pintype "unspecified"))
      (node (ref "LED25") (pin "3") (pinfunction "3_3") (pintype "unspecified"))
      (node (ref "LED30") (pin "1") (pinfunction "1_1") (pintype "unspecified"))
      (node (ref "LED30") (pin "3") (pinfunction "3_3") (pintype "unspecified"))
      (node (ref "LED35") (pin "1") (pinfunction "1_1") (pintype "unspecified"))
      (node (ref "LED35") (pin "3") (pinfunction "3_3") (pintype "unspecified"))
      (node (ref "LED5") (pin "1") (pinfunction "1_1") (pintype "unspecified"))
      (node (ref "LED5") (pin "3") (pinfunction "3_3") (pintype "unspecified"))
      (node (ref "U1") (pin "5") (pinfunction "5_5") (pintype "unspecified"))
    )
    (net (code "6") (name "/C5") (class "Default")
      (node (ref "LED36") (pin "1") (pinfunction "1_1") (pintype "unspecified"))
      (node (ref "LED36") (pin "3") (pinfunction "3_3") (pintype "unspecified"))
      (node (ref "LED41") (pin "1") (pinfunction "1_1") (pintype "unspecified"))
      (node (ref "LED41") (pin "3") (pinfunction "3_3") (pintype "unspecified"))
      (node (ref "LED46") (pin "1") (pinfunction "1_1") (pintype "unspecified"))
      (node (ref "LED46") (pin "3") (pinfunction "3_3") (pintype "unspecified"))
      (node (ref "LED51") (pin "1") (pinfunction "1_1") (pintype "unspecified"))
      (node (ref "LED51") (pin "3") (pinfunction "3_3") (pintype "unspecified"))
      (node (ref "LED56") (pin "1") (pinfunction "1_1") (pintype "unspecified"))
      (node (ref "LED56") (pin "3") (pinfunction "3_3") (pintype "unspecified"))
      (node (ref "LED61") (pin "1") (pinfunction "1_1") (pintype "unspecified"))
      (node (ref "LED61") (pin "3") (pinfunction "3_3") (pintype "unspecified"))
      (node (ref "LED66") (pin "1") (pinfunction "1_1") (pintype "unspecified"))
      (node (ref "LED66") (pin "3") (pinfunction "3_3") (pintype "unspecified"))
      (node (ref "U1") (pin "6") (pinfunction "6_6") (pintype "unspecified"))
    )
    (net (code "7") (name "/C6") (class "Default")
      (node (ref "LED37") (pin "1") (pinfunction "1_1") (pintype "unspecified"))
      (node (ref "LED37") (pin "3") (pinfunction "3_3") (pintype "unspecified"))
      (node (ref "LED42") (pin "1") (pinfunction "1_1") (pintype "unspecified"))
      (node (ref "LED42") (pin "3") (pinfunction "3_3") (pintype "unspecified"))
      (node (ref "LED47") (pin "1") (pinfunction "1_1") (pintype "unspecified"))
      (node (ref "LED47") (pin "3") (pinfunction "3_3") (pintype "unspecified"))
      (node (ref "LED52") (pin "1") (pinfunction "1_1") (pintype "unspecified"))
      (node (ref "LED52") (pin "3") (pinfunction "3_3") (pintype "unspecified"))
      (node (ref "LED57") (pin "1") (pinfunction "1_1") (pintype "unspecified"))
      (node (ref "LED57") (pin "3") (pinfunction "3_3") (pintype "unspecified"))
      (node (ref "LED62") (pin "1") (pinfunction "1_1") (pintype "unspecified"))
      (node (ref "LED62") (pin "3") (pinfunction "3_3") (pintype "unspecified"))
      (node (ref "LED67") (pin "1") (pinfunction "1_1") (pintype "unspecified"))
      (node (ref "LED67") (pin "3") (pinfunction "3_3") (pintype "unspecified"))
      (node (ref "U1") (pin "7") (pinfunction "7_7") (pintype "unspecified"))
    )
    (net (code "8") (name "/C7") (class "Default")
      (node (ref "LED38") (pin "1") (pinfunction "1_1") (pintype "unspecified"))
      (node (ref "LED38") (pin "3") (pinfunction "3_3") (pintype "unspecified"))
      (node (ref "LED43") (pin "1") (pinfunction "1_1") (pintype "unspecified"))
      (node (ref "LED43") (pin "3") (pinfunction "3_3") (pintype "unspecified"))
      (node (ref "LED48") (pin "1") (pinfunction "1_1") (pintype "unspecified"))
      (node (ref "LED48") (pin "3") (pinfunction "3_3") (pintype "unspecified"))
      (node (ref "LED53") (pin "1") (pinfunction "1_1") (pintype "unspecified"))
      (node (ref "LED53") (pin "3") (pinfunction "3_3") (pintype "unspecified"))
      (node (ref "LED58") (pin "1") (pinfunction "1_1") (pintype "unspecified"))
      (node (ref "LED58") (pin "3") (pinfunction "3_3") (pintype "unspecified"))
      (node (ref "LED63") (pin "1") (pinfunction "1_1") (pintype "unspecified"))
      (node (ref "LED63") (pin "3") (pinfunction "3_3") (pintype "unspecified"))
      (node (ref "LED68") (pin "1") (pinfunction "1_1") (pintype "unspecified"))
      (node (ref "LED68") (pin "3") (pinfunction "3_3") (pintype "unspecified"))
      (node (ref "U1") (pin "8") (pinfunction "8_8") (pintype "unspecified"))
    )
    (net (code "9") (name "/C8") (class "Default")
      (node (ref "LED39") (pin "1") (pinfunction "1_1") (pintype "unspecified"))
      (node (ref "LED39") (pin "3") (pinfunction "3_3") (pintype "unspecified"))
      (node (ref "LED44") (pin "1") (pinfunction "1_1") (pintype "unspecified"))
      (node (ref "LED44") (pin "3") (pinfunction "3_3") (pintype "unspecified"))
      (node (ref "LED49") (pin "1") (pinfunction "1_1") (pintype "unspecified"))
      (node (ref "LED49") (pin "3") (pinfunction "3_3") (pintype "unspecified"))
      (node (ref "LED54") (pin "1") (pinfunction "1_1") (pintype "unspecified"))
      (node (ref "LED54") (pin "3") (pinfunction "3_3") (pintype "unspecified"))
      (node (ref "LED59") (pin "1") (pinfunction "1_1") (pintype "unspecified"))
      (node (ref "LED59") (pin "3") (pinfunction "3_3") (pintype "unspecified"))
      (node (ref "LED64") (pin "1") (pinfunction "1_1") (pintype "unspecified"))
      (node (ref "LED64") (pin "3") (pinfunction "3_3") (pintype "unspecified"))
      (node (ref "LED69") (pin "1") (pinfunction "1_1") (pintype "unspecified"))
      (node (ref "LED69") (pin "3") (pinfunction "3_3") (pintype "unspecified"))
      (node (ref "U1") (pin "9") (pinfunction "9_9") (pintype "unspecified"))
    )
    (net (code "10") (name "/C9") (class "Default")
      (node (ref "LED40") (pin "1") (pinfunction "1_1") (pintype "unspecified"))
      (node (ref "LED40") (pin "3") (pinfunction "3_3") (pintype "unspecified"))
      (node (ref "LED45") (pin "1") (pinfunction "1_1") (pintype "unspecified"))
      (node (ref "LED45") (pin "3") (pinfunction "3_3") (pintype "unspecified"))
      (node (ref "LED50") (pin "1") (pinfunction "1_1") (pintype "unspecified"))
      (node (ref "LED50") (pin "3") (pinfunction "3_3") (pintype "unspecified"))
      (node (ref "LED55") (pin "1") (pinfunction "1_1") (pintype "unspecified"))
      (node (ref "LED55") (pin "3") (pinfunction "3_3") (pintype "unspecified"))
      (node (ref "LED60") (pin "1") (pinfunction "1_1") (pintype "unspecified"))
      (node (ref "LED60") (pin "3") (pinfunction "3_3") (pintype "unspecified"))
      (node (ref "LED65") (pin "1") (pinfunction "1_1") (pintype "unspecified"))
      (node (ref "LED65") (pin "3") (pinfunction "3_3") (pintype "unspecified"))
      (node (ref "LED70") (pin "1") (pinfunction "1_1") (pintype "unspecified"))
      (node (ref "LED70") (pin "3") (pinfunction "3_3") (pintype "unspecified"))
      (node (ref "U1") (pin "10") (pinfunction "10_10") (pintype "unspecified"))
    )
    (net (code "11") (name "/C10") (class "Default")
      (node (ref "LED101") (pin "1") (pinfunction "1_1") (pintype "unspecified"))
      (node (ref "LED101") (pin "3") (pinfunction "3_3") (pintype "unspecified"))
      (node (ref "LED71") (pin "1") (pinfunction "1_1") (pintype "unspecified"))
      (node (ref "LED71") (pin "3") (pinfunction "3_3") (pintype "unspecified"))
      (node (ref "LED76") (pin "1") (pinfunction "1_1") (pintype "unspecified"))
      (node (ref "LED76") (pin "3") (pinfunction "3_3") (pintype "unspecified"))
      (node (ref "LED81") (pin "1") (pinfunction "1_1") (pintype "unspecified"))
      (node (ref "LED81") (pin "3") (pinfunction "3_3") (pintype "unspecified"))
      (node (ref "LED86") (pin "1") (pinfunction "1_1") (pintype "unspecified"))
      (node (ref "LED86") (pin "3") (pinfunction "3_3") (pintype "unspecified"))
      (node (ref "LED91") (pin "1") (pinfunction "1_1") (pintype "unspecified"))
      (node (ref "LED91") (pin "3") (pinfunction "3_3") (pintype "unspecified"))
      (node (ref "LED96") (pin "1") (pinfunction "1_1") (pintype "unspecified"))
      (node (ref "LED96") (pin "3") (pinfunction "3_3") (pintype "unspecified"))
      (node (ref "U1") (pin "11") (pinfunction "11_11") (pintype "unspecified"))
    )
    (net (code "12") (name "/C11") (class "Default")
      (node (ref "LED102") (pin "1") (pinfunction "1_1") (pintype "unspecified"))
      (node (ref "LED102") (pin "3") (pinfunction "3_3") (pintype "unspecified"))
      (node (ref "LED72") (pin "1") (pinfunction "1_1") (pintype "unspecified"))
      (node (ref "LED72") (pin "3") (pinfunction "3_3") (pintype "unspecified"))
      (node (ref "LED77") (pin "1") (pinfunction "1_1") (pintype "unspecified"))
      (node (ref "LED77") (pin "3") (pinfunction "3_3") (pintype "unspecified"))
      (node (ref "LED82") (pin "1") (pinfunction "1_1") (pintype "unspecified"))
      (node (ref "LED82") (pin "3") (pinfunction "3_3") (pintype "unspecified"))
      (node (ref "LED87") (pin "1") (pinfunction "1_1") (pintype "unspecified"))
      (node (ref "LED87") (pin "3") (pinfunction "3_3") (pintype "unspecified"))
      (node (ref "LED92") (pin "1") (pinfunction "1_1") (pintype "unspecified"))
      (node (ref "LED92") (pin "3") (pinfunction "3_3") (pintype "unspecified"))
      (node (ref "LED97") (pin "1") (pinfunction "1_1") (pintype "unspecified"))
      (node (ref "LED97") (pin "3") (pinfunction "3_3") (pintype "unspecified"))
      (node (ref "U1") (pin "12") (pinfunction "12_12") (pintype "unspecified"))
    )
    (net (code "13") (name "/C12") (class "Default")
      (node (ref "LED103") (pin "1") (pinfunction "1_1") (pintype "unspecified"))
      (node (ref "LED103") (pin "3") (pinfunction "3_3") (pintype "unspecified"))
      (node (ref "LED73") (pin "1") (pinfunction "1_1") (pintype "unspecified"))
      (node (ref "LED73") (pin "3") (pinfunction "3_3") (pintype "unspecified"))
      (node (ref "LED78") (pin "1") (pinfunction "1_1") (pintype "unspecified"))
      (node (ref "LED78") (pin "3") (pinfunction "3_3") (pintype "unspecified"))
      (node (ref "LED83") (pin "1") (pinfunction "1_1") (pintype "unspecified"))
      (node (ref "LED83") (pin "3") (pinfunction "3_3") (pintype "unspecified"))
      (node (ref "LED88") (pin "1") (pinfunction "1_1") (pintype "unspecified"))
      (node (ref "LED88") (pin "3") (pinfunction "3_3") (pintype "unspecified"))
      (node (ref "LED93") (pin "1") (pinfunction "1_1") (pintype "unspecified"))
      (node (ref "LED93") (pin "3") (pinfunction "3_3") (pintype "unspecified"))
      (node (ref "LED98") (pin "1") (pinfunction "1_1") (pintype "unspecified"))
      (node (ref "LED98") (pin "3") (pinfunction "3_3") (pintype "unspecified"))
      (node (ref "U1") (pin "13") (pinfunction "13_13") (pintype "unspecified"))
    )
    (net (code "14") (name "/C13") (class "Default")
      (node (ref "LED104") (pin "1") (pinfunction "1_1") (pintype "unspecified"))
      (node (ref "LED104") (pin "3") (pinfunction "3_3") (pintype "unspecified"))
      (node (ref "LED74") (pin "1") (pinfunction "1_1") (pintype "unspecified"))
      (node (ref "LED74") (pin "3") (pinfunction "3_3") (pintype "unspecified"))
      (node (ref "LED79") (pin "1") (pinfunction "1_1") (pintype "unspecified"))
      (node (ref "LED79") (pin "3") (pinfunction "3_3") (pintype "unspecified"))
      (node (ref "LED84") (pin "1") (pinfunction "1_1") (pintype "unspecified"))
      (node (ref "LED84") (pin "3") (pinfunction "3_3") (pintype "unspecified"))
      (node (ref "LED89") (pin "1") (pinfunction "1_1") (pintype "unspecified"))
      (node (ref "LED89") (pin "3") (pinfunction "3_3") (pintype "unspecified"))
      (node (ref "LED94") (pin "1") (pinfunction "1_1") (pintype "unspecified"))
      (node (ref "LED94") (pin "3") (pinfunction "3_3") (pintype "unspecified"))
      (node (ref "LED99") (pin "1") (pinfunction "1_1") (pintype "unspecified"))
      (node (ref "LED99") (pin "3") (pinfunction "3_3") (pintype "unspecified"))
      (node (ref "U1") (pin "14") (pinfunction "14_14") (pintype "unspecified"))
    )
    (net (code "15") (name "/C14") (class "Default")
      (node (ref "LED100") (pin "1") (pinfunction "1_1") (pintype "unspecified"))
      (node (ref "LED100") (pin "3") (pinfunction "3_3") (pintype "unspecified"))
      (node (ref "LED105") (pin "1") (pinfunction "1_1") (pintype "unspecified"))
      (node (ref "LED105") (pin "3") (pinfunction "3_3") (pintype "unspecified"))
      (node (ref "LED75") (pin "1") (pinfunction "1_1") (pintype "unspecified"))
      (node (ref "LED75") (pin "3") (pinfunction "3_3") (pintype "unspecified"))
      (node (ref "LED80") (pin "1") (pinfunction "1_1") (pintype "unspecified"))
      (node (ref "LED80") (pin "3") (pinfunction "3_3") (pintype "unspecified"))
      (node (ref "LED85") (pin "1") (pinfunction "1_1") (pintype "unspecified"))
      (node (ref "LED85") (pin "3") (pinfunction "3_3") (pintype "unspecified"))
      (node (ref "LED90") (pin "1") (pinfunction "1_1") (pintype "unspecified"))
      (node (ref "LED90") (pin "3") (pinfunction "3_3") (pintype "unspecified"))
      (node (ref "LED95") (pin "1") (pinfunction "1_1") (pintype "unspecified"))
      (node (ref "LED95") (pin "3") (pinfunction "3_3") (pintype "unspecified"))
      (node (ref "U1") (pin "15") (pinfunction "15_15") (pintype "unspecified"))
    )
    (net (code "16") (name "/R0_B") (class "Default")
      (node (ref "H1") (pin "2") (pinfunction "2_2") (pintype "unspecified"))
      (node (ref "LED1") (pin "4") (pinfunction "4_4") (pintype "unspecified"))
      (node (ref "LED2") (pin "4") (pinfunction "4_4") (pintype "unspecified"))
      (node (ref "LED3") (pin "4") (pinfunction "4_4") (pintype "unspecified"))
      (node (ref "LED36") (pin "4") (pinfunction "4_4") (pintype "unspecified"))
      (node (ref "LED37") (pin "4") (pinfunction "4_4") (pintype "unspecified"))
      (node (ref "LED38") (pin "4") (pinfunction "4_4") (pintype "unspecified"))
      (node (ref "LED39") (pin "4") (pinfunction "4_4") (pintype "unspecified"))
      (node (ref "LED4") (pin "4") (pinfunction "4_4") (pintype "unspecified"))
      (node (ref "LED40") (pin "4") (pinfunction "4_4") (pintype "unspecified"))
      (node (ref "LED5") (pin "4") (pinfunction "4_4") (pintype "unspecified"))
      (node (ref "LED71") (pin "4") (pinfunction "4_4") (pintype "unspecified"))
      (node (ref "LED72") (pin "4") (pinfunction "4_4") (pintype "unspecified"))
      (node (ref "LED73") (pin "4") (pinfunction "4_4") (pintype "unspecified"))
      (node (ref "LED74") (pin "4") (pinfunction "4_4") (pintype "unspecified"))
      (node (ref "LED75") (pin "4") (pinfunction "4_4") (pintype "unspecified"))
    )
    (net (code "17") (name "/R0_R") (class "Default")
      (node (ref "H1") (pin "1") (pinfunction "1_1") (pintype "unspecified"))
      (node (ref "LED1") (pin "2") (pinfunction "2_2") (pintype "unspecified"))
      (node (ref "LED2") (pin "2") (pinfunction "2_2") (pintype "unspecified"))
      (node (ref "LED3") (pin "2") (pinfunction "2_2") (pintype "unspecified"))
      (node (ref "LED36") (pin "2") (pinfunction "2_2") (pintype "unspecified"))
      (node (ref "LED37") (pin "2") (pinfunction "2_2") (pintype "unspecified"))
      (node (ref "LED38") (pin "2") (pinfunction "2_2") (pintype "unspecified"))
      (node (ref "LED39") (pin "2") (pinfunction "2_2") (pintype "unspecified"))
      (node (ref "LED4") (pin "2") (pinfunction "2_2") (pintype "unspecified"))
      (node (ref "LED40") (pin "2") (pinfunction "2_2") (pintype "unspecified"))
      (node (ref "LED5") (pin "2") (pinfunction "2_2") (pintype "unspecified"))
      (node (ref "LED71") (pin "2") (pinfunction "2_2") (pintype "unspecified"))
      (node (ref "LED72") (pin "2") (pinfunction "2_2") (pintype "unspecified"))
      (node (ref "LED73") (pin "2") (pinfunction "2_2") (pintype "unspecified"))
      (node (ref "LED74") (pin "2") (pinfunction "2_2") (pintype "unspecified"))
      (node (ref "LED75") (pin "2") (pinfunction "2_2") (pintype "unspecified"))
    )
    (net (code "18") (name "/R1_B") (class "Default")
      (node (ref "H1") (pin "4") (pinfunction "4_4") (pintype "unspecified"))
      (node (ref "LED10") (pin "4") (pinfunction "4_4") (pintype "unspecified"))
      (node (ref "LED41") (pin "4") (pinfunction "4_4") (pintype "unspecified"))
      (node (ref "LED42") (pin "4") (pinfunction "4_4") (pintype "unspecified"))
      (node (ref "LED43") (pin "4") (pinfunction "4_4") (pintype "unspecified"))
      (node (ref "LED44") (pin "4") (pinfunction "4_4") (pintype "unspecified"))
      (node (ref "LED45") (pin "4") (pinfunction "4_4") (pintype "unspecified"))
      (node (ref "LED6") (pin "4") (pinfunction "4_4") (pintype "unspecified"))
      (node (ref "LED7") (pin "4") (pinfunction "4_4") (pintype "unspecified"))
      (node (ref "LED76") (pin "4") (pinfunction "4_4") (pintype "unspecified"))
      (node (ref "LED77") (pin "4") (pinfunction "4_4") (pintype "unspecified"))
      (node (ref "LED78") (pin "4") (pinfunction "4_4") (pintype "unspecified"))
      (node (ref "LED79") (pin "4") (pinfunction "4_4") (pintype "unspecified"))
      (node (ref "LED8") (pin "4") (pinfunction "4_4") (pintype "unspecified"))
      (node (ref "LED80") (pin "4") (pinfunction "4_4") (pintype "unspecified"))
      (node (ref "LED9") (pin "4") (pinfunction "4_4") (pintype "unspecified"))
    )
    (net (code "19") (name "/R1_R") (class "Default")
      (node (ref "H1") (pin "3") (pinfunction "3_3") (pintype "unspecified"))
      (node (ref "LED10") (pin "2") (pinfunction "2_2") (pintype "unspecified"))
      (node (ref "LED41") (pin "2") (pinfunction "2_2") (pintype "unspecified"))
      (node (ref "LED42") (pin "2") (pinfunction "2_2") (pintype "unspecified"))
      (node (ref "LED43") (pin "2") (pinfunction "2_2") (pintype "unspecified"))
      (node (ref "LED44") (pin "2") (pinfunction "2_2") (pintype "unspecified"))
      (node (ref "LED45") (pin "2") (pinfunction "2_2") (pintype "unspecified"))
      (node (ref "LED6") (pin "2") (pinfunction "2_2") (pintype "unspecified"))
      (node (ref "LED7") (pin "2") (pinfunction "2_2") (pintype "unspecified"))
      (node (ref "LED76") (pin "2") (pinfunction "2_2") (pintype "unspecified"))
      (node (ref "LED77") (pin "2") (pinfunction "2_2") (pintype "unspecified"))
      (node (ref "LED78") (pin "2") (pinfunction "2_2") (pintype "unspecified"))
      (node (ref "LED79") (pin "2") (pinfunction "2_2") (pintype "unspecified"))
      (node (ref "LED8") (pin "2") (pinfunction "2_2") (pintype "unspecified"))
      (node (ref "LED80") (pin "2") (pinfunction "2_2") (pintype "unspecified"))
      (node (ref "LED9") (pin "2") (pinfunction "2_2") (pintype "unspecified"))
    )
    (net (code "20") (name "/R2_B") (class "Default")
      (node (ref "H1") (pin "6") (pinfunction "6_6") (pintype "unspecified"))
      (node (ref "LED11") (pin "4") (pinfunction "4_4") (pintype "unspecified"))
      (node (ref "LED12") (pin "4") (pinfunction "4_4") (pintype "unspecified"))
      (node (ref "LED13") (pin "4") (pinfunction "4_4") (pintype "unspecified"))
      (node (ref "LED14") (pin "4") (pinfunction "4_4") (pintype "unspecified"))
      (node (ref "LED15") (pin "4") (pinfunction "4_4") (pintype "unspecified"))
      (node (ref "LED46") (pin "4") (pinfunction "4_4") (pintype "unspecified"))
      (node (ref "LED47") (pin "4") (pinfunction "4_4") (pintype "unspecified"))
      (node (ref "LED48") (pin "4") (pinfunction "4_4") (pintype "unspecified"))
      (node (ref "LED49") (pin "4") (pinfunction "4_4") (pintype "unspecified"))
      (node (ref "LED50") (pin "4") (pinfunction "4_4") (pintype "unspecified"))
      (node (ref "LED81") (pin "4") (pinfunction "4_4") (pintype "unspecified"))
      (node (ref "LED82") (pin "4") (pinfunction "4_4") (pintype "unspecified"))
      (node (ref "LED83") (pin "4") (pinfunction "4_4") (pintype "unspecified"))
      (node (ref "LED84") (pin "4") (pinfunction "4_4") (pintype "unspecified"))
      (node (ref "LED85") (pin "4") (pinfunction "4_4") (pintype "unspecified"))
    )
    (net (code "21") (name "/R2_R") (class "Default")
      (node (ref "H1") (pin "5") (pinfunction "5_5") (pintype "unspecified"))
      (node (ref "LED11") (pin "2") (pinfunction "2_2") (pintype "unspecified"))
      (node (ref "LED12") (pin "2") (pinfunction "2_2") (pintype "unspecified"))
      (node (ref "LED13") (pin "2") (pinfunction "2_2") (pintype "unspecified"))
      (node (ref "LED14") (pin "2") (pinfunction "2_2") (pintype "unspecified"))
      (node (ref "LED15") (pin "2") (pinfunction "2_2") (pintype "unspecified"))
      (node (ref "LED46") (pin "2") (pinfunction "2_2") (pintype "unspecified"))
      (node (ref "LED47") (pin "2") (pinfunction "2_2") (pintype "unspecified"))
      (node (ref "LED48") (pin "2") (pinfunction "2_2") (pintype "unspecified"))
      (node (ref "LED49") (pin "2") (pinfunction "2_2") (pintype "unspecified"))
      (node (ref "LED50") (pin "2") (pinfunction "2_2") (pintype "unspecified"))
      (node (ref "LED81") (pin "2") (pinfunction "2_2") (pintype "unspecified"))
      (node (ref "LED82") (pin "2") (pinfunction "2_2") (pintype "unspecified"))
      (node (ref "LED83") (pin "2") (pinfunction "2_2") (pintype "unspecified"))
      (node (ref "LED84") (pin "2") (pinfunction "2_2") (pintype "unspecified"))
      (node (ref "LED85") (pin "2") (pinfunction "2_2") (pintype "unspecified"))
    )
    (net (code "22") (name "/R3_B") (class "Default")
      (node (ref "H1") (pin "8") (pinfunction "8_8") (pintype "unspecified"))
      (node (ref "LED16") (pin "4") (pinfunction "4_4") (pintype "unspecified"))
      (node (ref "LED17") (pin "4") (pinfunction "4_4") (pintype "unspecified"))
      (node (ref "LED18") (pin "4") (pinfunction "4_4") (pintype "unspecified"))
      (node (ref "LED19") (pin "4") (pinfunction "4_4") (pintype "unspecified"))
      (node (ref "LED20") (pin "4") (pinfunction "4_4") (pintype "unspecified"))
      (node (ref "LED51") (pin "4") (pinfunction "4_4") (pintype "unspecified"))
      (node (ref "LED52") (pin "4") (pinfunction "4_4") (pintype "unspecified"))
      (node (ref "LED53") (pin "4") (pinfunction "4_4") (pintype "unspecified"))
      (node (ref "LED54") (pin "4") (pinfunction "4_4") (pintype "unspecified"))
      (node (ref "LED55") (pin "4") (pinfunction "4_4") (pintype "unspecified"))
      (node (ref "LED86") (pin "4") (pinfunction "4_4") (pintype "unspecified"))
      (node (ref "LED87") (pin "4") (pinfunction "4_4") (pintype "unspecified"))
      (node (ref "LED88") (pin "4") (pinfunction "4_4") (pintype "unspecified"))
      (node (ref "LED89") (pin "4") (pinfunction "4_4") (pintype "unspecified"))
      (node (ref "LED90") (pin "4") (pinfunction "4_4") (pintype "unspecified"))
    )
    (net (code "23") (name "/R3_R") (class "Default")
      (node (ref "H1") (pin "7") (pinfunction "7_7") (pintype "unspecified"))
      (node (ref "LED16") (pin "2") (pinfunction "2_2") (pintype "unspecified"))
      (node (ref "LED17") (pin "2") (pinfunction "2_2") (pintype "unspecified"))
      (node (ref "LED18") (pin "2") (pinfunction "2_2") (pintype "unspecified"))
      (node (ref "LED19") (pin "2") (pinfunction "2_2") (pintype "unspecified"))
      (node (ref "LED20") (pin "2") (pinfunction "2_2") (pintype "unspecified"))
      (node (ref "LED51") (pin "2") (pinfunction "2_2") (pintype "unspecified"))
      (node (ref "LED52") (pin "2") (pinfunction "2_2") (pintype "unspecified"))
      (node (ref "LED53") (pin "2") (pinfunction "2_2") (pintype "unspecified"))
      (node (ref "LED54") (pin "2") (pinfunction "2_2") (pintype "unspecified"))
      (node (ref "LED55") (pin "2") (pinfunction "2_2") (pintype "unspecified"))
      (node (ref "LED86") (pin "2") (pinfunction "2_2") (pintype "unspecified"))
      (node (ref "LED87") (pin "2") (pinfunction "2_2") (pintype "unspecified"))
      (node (ref "LED88") (pin "2") (pinfunction "2_2") (pintype "unspecified"))
      (node (ref "LED89") (pin "2") (pinfunction "2_2") (pintype "unspecified"))
      (node (ref "LED90") (pin "2") (pinfunction "2_2") (pintype "unspecified"))
    )
    (net (code "24") (name "/R4_B") (class "Default")
      (node (ref "H1") (pin "10") (pinfunction "10_10") (pintype "unspecified"))
      (node (ref "LED21") (pin "4") (pinfunction "4_4") (pintype "unspecified"))
      (node (ref "LED22") (pin "4") (pinfunction "4_4") (pintype "unspecified"))
      (node (ref "LED23") (pin "4") (pinfunction "4_4") (pintype "unspecified"))
      (node (ref "LED24") (pin "4") (pinfunction "4_4") (pintype "unspecified"))
      (node (ref "LED25") (pin "4") (pinfunction "4_4") (pintype "unspecified"))
      (node (ref "LED56") (pin "4") (pinfunction "4_4") (pintype "unspecified"))
      (node (ref "LED57") (pin "4") (pinfunction "4_4") (pintype "unspecified"))
      (node (ref "LED58") (pin "4") (pinfunction "4_4") (pintype "unspecified"))
      (node (ref "LED59") (pin "4") (pinfunction "4_4") (pintype "unspecified"))
      (node (ref "LED60") (pin "4") (pinfunction "4_4") (pintype "unspecified"))
      (node (ref "LED91") (pin "4") (pinfunction "4_4") (pintype "unspecified"))
      (node (ref "LED92") (pin "4") (pinfunction "4_4") (pintype "unspecified"))
      (node (ref "LED93") (pin "4") (pinfunction "4_4") (pintype "unspecified"))
      (node (ref "LED94") (pin "4") (pinfunction "4_4") (pintype "unspecified"))
      (node (ref "LED95") (pin "4") (pinfunction "4_4") (pintype "unspecified"))
    )
    (net (code "25") (name "/R4_R") (class "Default")
      (node (ref "H1") (pin "9") (pinfunction "9_9") (pintype "unspecified"))
      (node (ref "LED21") (pin "2") (pinfunction "2_2") (pintype "unspecified"))
      (node (ref "LED22") (pin "2") (pinfunction "2_2") (pintype "unspecified"))
      (node (ref "LED23") (pin "2") (pinfunction "2_2") (pintype "unspecified"))
      (node (ref "LED24") (pin "2") (pinfunction "2_2") (pintype "unspecified"))
      (node (ref "LED25") (pin "2") (pinfunction "2_2") (pintype "unspecified"))
      (node (ref "LED56") (pin "2") (pinfunction "2_2") (pintype "unspecified"))
      (node (ref "LED57") (pin "2") (pinfunction "2_2") (pintype "unspecified"))
      (node (ref "LED58") (pin "2") (pinfunction "2_2") (pintype "unspecified"))
      (node (ref "LED59") (pin "2") (pinfunction "2_2") (pintype "unspecified"))
      (node (ref "LED60") (pin "2") (pinfunction "2_2") (pintype "unspecified"))
      (node (ref "LED91") (pin "2") (pinfunction "2_2") (pintype "unspecified"))
      (node (ref "LED92") (pin "2") (pinfunction "2_2") (pintype "unspecified"))
      (node (ref "LED93") (pin "2") (pinfunction "2_2") (pintype "unspecified"))
      (node (ref "LED94") (pin "2") (pinfunction "2_2") (pintype "unspecified"))
      (node (ref "LED95") (pin "2") (pinfunction "2_2") (pintype "unspecified"))
    )
    (net (code "26") (name "/R5_B") (class "Default")
      (node (ref "H1") (pin "12") (pinfunction "12_12") (pintype "unspecified"))
      (node (ref "LED100") (pin "4") (pinfunction "4_4") (pintype "unspecified"))
      (node (ref "LED26") (pin "4") (pinfunction "4_4") (pintype "unspecified"))
      (node (ref "LED27") (pin "4") (pinfunction "4_4") (pintype "unspecified"))
      (node (ref "LED28") (pin "4") (pinfunction "4_4") (pintype "unspecified"))
      (node (ref "LED29") (pin "4") (pinfunction "4_4") (pintype "unspecified"))
      (node (ref "LED30") (pin "4") (pinfunction "4_4") (pintype "unspecified"))
      (node (ref "LED61") (pin "4") (pinfunction "4_4") (pintype "unspecified"))
      (node (ref "LED62") (pin "4") (pinfunction "4_4") (pintype "unspecified"))
      (node (ref "LED63") (pin "4") (pinfunction "4_4") (pintype "unspecified"))
      (node (ref "LED64") (pin "4") (pinfunction "4_4") (pintype "unspecified"))
      (node (ref "LED65") (pin "4") (pinfunction "4_4") (pintype "unspecified"))
      (node (ref "LED96") (pin "4") (pinfunction "4_4") (pintype "unspecified"))
      (node (ref "LED97") (pin "4") (pinfunction "4_4") (pintype "unspecified"))
      (node (ref "LED98") (pin "4") (pinfunction "4_4") (pintype "unspecified"))
      (node (ref "LED99") (pin "4") (pinfunction "4_4") (pintype "unspecified"))
    )
    (net (code "27") (name "/R5_R") (class "Default")
      (node (ref "H1") (pin "11") (pinfunction "11_11") (pintype "unspecified"))
      (node (ref "LED100") (pin "2") (pinfunction "2_2") (pintype "unspecified"))
      (node (ref "LED26") (pin "2") (pinfunction "2_2") (pintype "unspecified"))
      (node (ref "LED27") (pin "2") (pinfunction "2_2") (pintype "unspecified"))
      (node (ref "LED28") (pin "2") (pinfunction "2_2") (pintype "unspecified"))
      (node (ref "LED29") (pin "2") (pinfunction "2_2") (pintype "unspecified"))
      (node (ref "LED30") (pin "2") (pinfunction "2_2") (pintype "unspecified"))
      (node (ref "LED61") (pin "2") (pinfunction "2_2") (pintype "unspecified"))
      (node (ref "LED62") (pin "2") (pinfunction "2_2") (pintype "unspecified"))
      (node (ref "LED63") (pin "2") (pinfunction "2_2") (pintype "unspecified"))
      (node (ref "LED64") (pin "2") (pinfunction "2_2") (pintype "unspecified"))
      (node (ref "LED65") (pin "2") (pinfunction "2_2") (pintype "unspecified"))
      (node (ref "LED96") (pin "2") (pinfunction "2_2") (pintype "unspecified"))
      (node (ref "LED97") (pin "2") (pinfunction "2_2") (pintype "unspecified"))
      (node (ref "LED98") (pin "2") (pinfunction "2_2") (pintype "unspecified"))
      (node (ref "LED99") (pin "2") (pinfunction "2_2") (pintype "unspecified"))
    )
    (net (code "28") (name "/R6_B") (class "Default")
      (node (ref "H1") (pin "14") (pinfunction "14_14") (pintype "unspecified"))
      (node (ref "LED101") (pin "4") (pinfunction "4_4") (pintype "unspecified"))
      (node (ref "LED102") (pin "4") (pinfunction "4_4") (pintype "unspecified"))
      (node (ref "LED103") (pin "4") (pinfunction "4_4") (pintype "unspecified"))
      (node (ref "LED104") (pin "4") (pinfunction "4_4") (pintype "unspecified"))
      (node (ref "LED105") (pin "4") (pinfunction "4_4") (pintype "unspecified"))
      (node (ref "LED31") (pin "4") (pinfunction "4_4") (pintype "unspecified"))
      (node (ref "LED32") (pin "4") (pinfunction "4_4") (pintype "unspecified"))
      (node (ref "LED33") (pin "4") (pinfunction "4_4") (pintype "unspecified"))
      (node (ref "LED34") (pin "4") (pinfunction "4_4") (pintype "unspecified"))
      (node (ref "LED35") (pin "4") (pinfunction "4_4") (pintype "unspecified"))
      (node (ref "LED66") (pin "4") (pinfunction "4_4") (pintype "unspecified"))
      (node (ref "LED67") (pin "4") (pinfunction "4_4") (pintype "unspecified"))
      (node (ref "LED68") (pin "4") (pinfunction "4_4") (pintype "unspecified"))
      (node (ref "LED69") (pin "4") (pinfunction "4_4") (pintype "unspecified"))
      (node (ref "LED70") (pin "4") (pinfunction "4_4") (pintype "unspecified"))
    )
    (net (code "29") (name "/R6_R") (class "Default")
      (node (ref "H1") (pin "13") (pinfunction "13_13") (pintype "unspecified"))
      (node (ref "LED101") (pin "2") (pinfunction "2_2") (pintype "unspecified"))
      (node (ref "LED102") (pin "2") (pinfunction "2_2") (pintype "unspecified"))
      (node (ref "LED103") (pin "2") (pinfunction "2_2") (pintype "unspecified"))
      (node (ref "LED104") (pin "2") (pinfunction "2_2") (pintype "unspecified"))
      (node (ref "LED105") (pin "2") (pinfunction "2_2") (pintype "unspecified"))
      (node (ref "LED31") (pin "2") (pinfunction "2_2") (pintype "unspecified"))
      (node (ref "LED32") (pin "2") (pinfunction "2_2") (pintype "unspecified"))
      (node (ref "LED33") (pin "2") (pinfunction "2_2") (pintype "unspecified"))
      (node (ref "LED34") (pin "2") (pinfunction "2_2") (pintype "unspecified"))
      (node (ref "LED35") (pin "2") (pinfunction "2_2") (pintype "unspecified"))
      (node (ref "LED66") (pin "2") (pinfunction "2_2") (pintype "unspecified"))
      (node (ref "LED67") (pin "2") (pinfunction "2_2") (pintype "unspecified"))
      (node (ref "LED68") (pin "2") (pinfunction "2_2") (pintype "unspecified"))
      (node (ref "LED69") (pin "2") (pinfunction "2_2") (pintype "unspecified"))
      (node (ref "LED70") (pin "2") (pinfunction "2_2") (pintype "unspecified"))
    )
  )
)
